# I2C_buttons.net
KiCad netlist of a schematic drawn in EAGLE
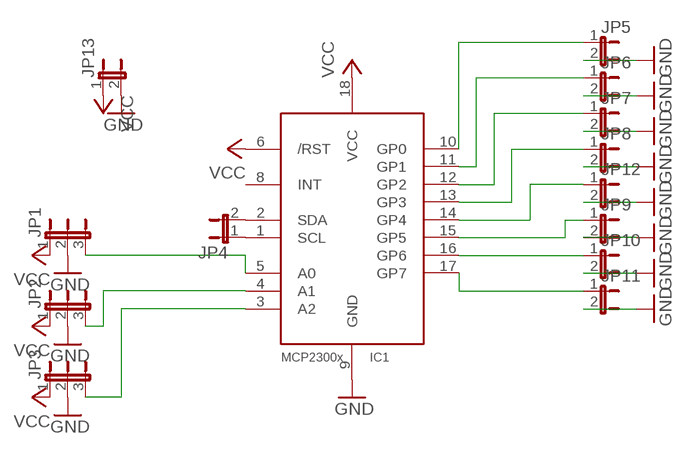
[diagram p0: schematic, sheet 1]

(export (version "E")
  (design (tool "Eeschema 10.0.6"))
  (components
    (comp (ref "IC1")
      (value "MCP23008/P")
      (footprint "eagle-import:DIL18")
      (libsource (lib "eagle-import") (part "MCP23008/P"))
    )
    (comp (ref "JP1")
      (value "JP2E")
      (footprint "eagle-import:JP2")
      (libsource (lib "eagle-import") (part "JP2E"))
    )
    (comp (ref "JP2")
      (value "JP2E")
      (footprint "eagle-import:JP2")
      (libsource (lib "eagle-import") (part "JP2E"))
    )
    (comp (ref "JP3")
      (value "JP2E")
      (footprint "eagle-import:JP2")
      (libsource (lib "eagle-import") (part "JP2E"))
    )
    (comp (ref "JP4")
      (value "JP1E")
      (footprint "eagle-import:JP1")
      (libsource (lib "eagle-import") (part "JP1E"))
    )
    (comp (ref "JP5")
      (value "JP1E")
      (footprint "eagle-import:JP1")
      (libsource (lib "eagle-import") (part "JP1E"))
    )
    (comp (ref "JP6")
      (value "JP1E")
      (footprint "eagle-import:JP1")
      (libsource (lib "eagle-import") (part "JP1E"))
    )
    (comp (ref "JP7")
      (value "JP1E")
      (footprint "eagle-import:JP1")
      (libsource (lib "eagle-import") (part "JP1E"))
    )
    (comp (ref "JP8")
      (value "JP1E")
      (footprint "eagle-import:JP1")
      (libsource (lib "eagle-import") (part "JP1E"))
    )
    (comp (ref "JP9")
      (value "JP1E")
      (footprint "eagle-import:JP1")
      (libsource (lib "eagle-import") (part "JP1E"))
    )
    (comp (ref "JP10")
      (value "JP1E")
      (footprint "eagle-import:JP1")
      (libsource (lib "eagle-import") (part "JP1E"))
    )
    (comp (ref "JP11")
      (value "JP1E")
      (footprint "eagle-import:JP1")
      (libsource (lib "eagle-import") (part "JP1E"))
    )
    (comp (ref "JP12")
      (value "JP1E")
      (footprint "eagle-import:JP1")
      (libsource (lib "eagle-import") (part "JP1E"))
    )
    (comp (ref "JP13")
      (value "JP1E")
      (footprint "eagle-import:JP1")
      (libsource (lib "eagle-import") (part "JP1E"))
    )
  )
  (nets
    (net (code "1") (name "GND") (class "Default")
      (node (ref "IC1") (pin "9") (pinfunction "GND_9") (pintype "power_in"))
      (node (ref "JP1") (pin "2") (pinfunction "2_2") (pintype "passive"))
      (node (ref "JP10") (pin "2") (pinfunction "2_2") (pintype "passive"))
      (node (ref "JP11") (pin "2") (pinfunction "2_2") (pintype "passive"))
      (node (ref "JP12") (pin "2") (pinfunction "2_2") (pintype "passive"))
      (node (ref "JP13") (pin "2") (pinfunction "2_2") (pintype "passive"))
      (node (ref "JP2") (pin "2") (pinfunction "2_2") (pintype "passive"))
      (node (ref "JP3") (pin "2") (pinfunction "2_2") (pintype "passive"))
      (node (ref "JP5") (pin "2") (pinfunction "2_2") (pintype "passive"))
      (node (ref "JP6") (pin "2") (pinfunction "2_2") (pintype "passive"))
      (node (ref "JP7") (pin "2") (pinfunction "2_2") (pintype "passive"))
      (node (ref "JP8") (pin "2") (pinfunction "2_2") (pintype "passive"))
      (node (ref "JP9") (pin "2") (pinfunction "2_2") (pintype "passive"))
    )
    (net (code "2") (name "Net-(IC1-A0)") (class "Default")
      (node (ref "IC1") (pin "5") (pinfunction "A0_5") (pintype "input"))
      (node (ref "JP1") (pin "3") (pinfunction "3_3") (pintype "passive"))
    )
    (net (code "3") (name "Net-(IC1-A1)") (class "Default")
      (node (ref "IC1") (pin "4") (pinfunction "A1_4") (pintype "input"))
      (node (ref "JP2") (pin "3") (pinfunction "3_3") (pintype "passive"))
    )
    (net (code "4") (name "Net-(IC1-A2)") (class "Default")
      (node (ref "IC1") (pin "3") (pinfunction "A2_3") (pintype "input"))
      (node (ref "JP3") (pin "3") (pinfunction "3_3") (pintype "passive"))
    )
    (net (code "5") (name "Net-(IC1-GP0)") (class "Default")
      (node (ref "IC1") (pin "10") (pinfunction "GP0_10") (pintype "bidirectional"))
      (node (ref "JP5") (pin "1") (pinfunction "1_1") (pintype "passive"))
    )
    (net (code "6") (name "Net-(IC1-GP1)") (class "Default")
      (node (ref "IC1") (pin "11") (pinfunction "GP1_11") (pintype "bidirectional"))
      (node (ref "JP6") (pin "1") (pinfunction "1_1") (pintype "passive"))
    )
    (net (code "7") (name "Net-(IC1-GP2)") (class "Default")
      (node (ref "IC1") (pin "12") (pinfunction "GP2_12") (pintype "bidirectional"))
      (node (ref "JP7") (pin "1") (pinfunction "1_1") (pintype "passive"))
    )
    (net (code "8") (name "Net-(IC1-GP3)") (class "Default")
      (node (ref "IC1") (pin "13") (pinfunction "GP3_13") (pintype "bidirectional"))
      (node (ref "JP8") (pin "1") (pinfunction "1_1") (pintype "passive"))
    )
    (net (code "9") (name "Net-(IC1-GP4)") (class "Default")
      (node (ref "IC1") (pin "14") (pinfunction "GP4_14") (pintype "bidirectional"))
      (node (ref "JP12") (pin "1") (pinfunction "1_1") (pintype "passive"))
    )
    (net (code "10") (name "Net-(IC1-GP5)") (class "Default")
      (node (ref "IC1") (pin "15") (pinfunction "GP5_15") (pintype "bidirectional"))
      (node (ref "JP9") (pin "1") (pinfunction "1_1") (pintype "passive"))
    )
    (net (code "11") (name "Net-(IC1-GP6)") (class "Default")
      (node (ref "IC1") (pin "16") (pinfunction "GP6_16") (pintype "bidirectional"))
      (node (ref "JP10") (pin "1") (pinfunction "1_1") (pintype "passive"))
    )
    (net (code "12") (name "Net-(IC1-GP7)") (class "Default")
      (node (ref "IC1") (pin "17") (pinfunction "GP7_17") (pintype "bidirectional"))
      (node (ref "JP11") (pin "1") (pinfunction "1_1") (pintype "passive"))
    )
    (net (code "13") (name "Net-(IC1-SCL)") (class "Default")
      (node (ref "IC1") (pin "1") (pinfunction "SCL_1") (pintype "bidirectional"))
      (node (ref "JP4") (pin "1") (pinfunction "1_1") (pintype "passive"))
    )
    (net (code "14") (name "Net-(IC1-SDA)") (class "Default")
      (node (ref "IC1") (pin "2") (pinfunction "SDA_2") (pintype "bidirectional"))
      (node (ref "JP4") (pin "2") (pinfunction "2_2") (pintype "passive"))
    )
    (net (code "15") (name "VCC") (class "Default")
      (node (ref "IC1") (pin "18") (pinfunction "VCC_18") (pintype "power_in"))
      (node (ref "IC1") (pin "6") (pinfunction "/RST_6") (pintype "input"))
      (node (ref "JP1") (pin "1") (pinfunction "1_1") (pintype "passive"))
      (node (ref "JP13") (pin "1") (pinfunction "1_1") (pintype "passive"))
      (node (ref "JP2") (pin "1") (pinfunction "1_1") (pintype "passive"))
      (node (ref "JP3") (pin "1") (pinfunction "1_1") (pintype "passive"))
    )
    (net (code "16") (name "unconnected-(IC1-INT-Pad8)") (class "Default")
      (node (ref "IC1") (pin "8") (pinfunction "INT_8") (pintype "output"))
    )
  )
)
